# Regulador.net
KiCad netlist of a schematic drawn in Altium Designer
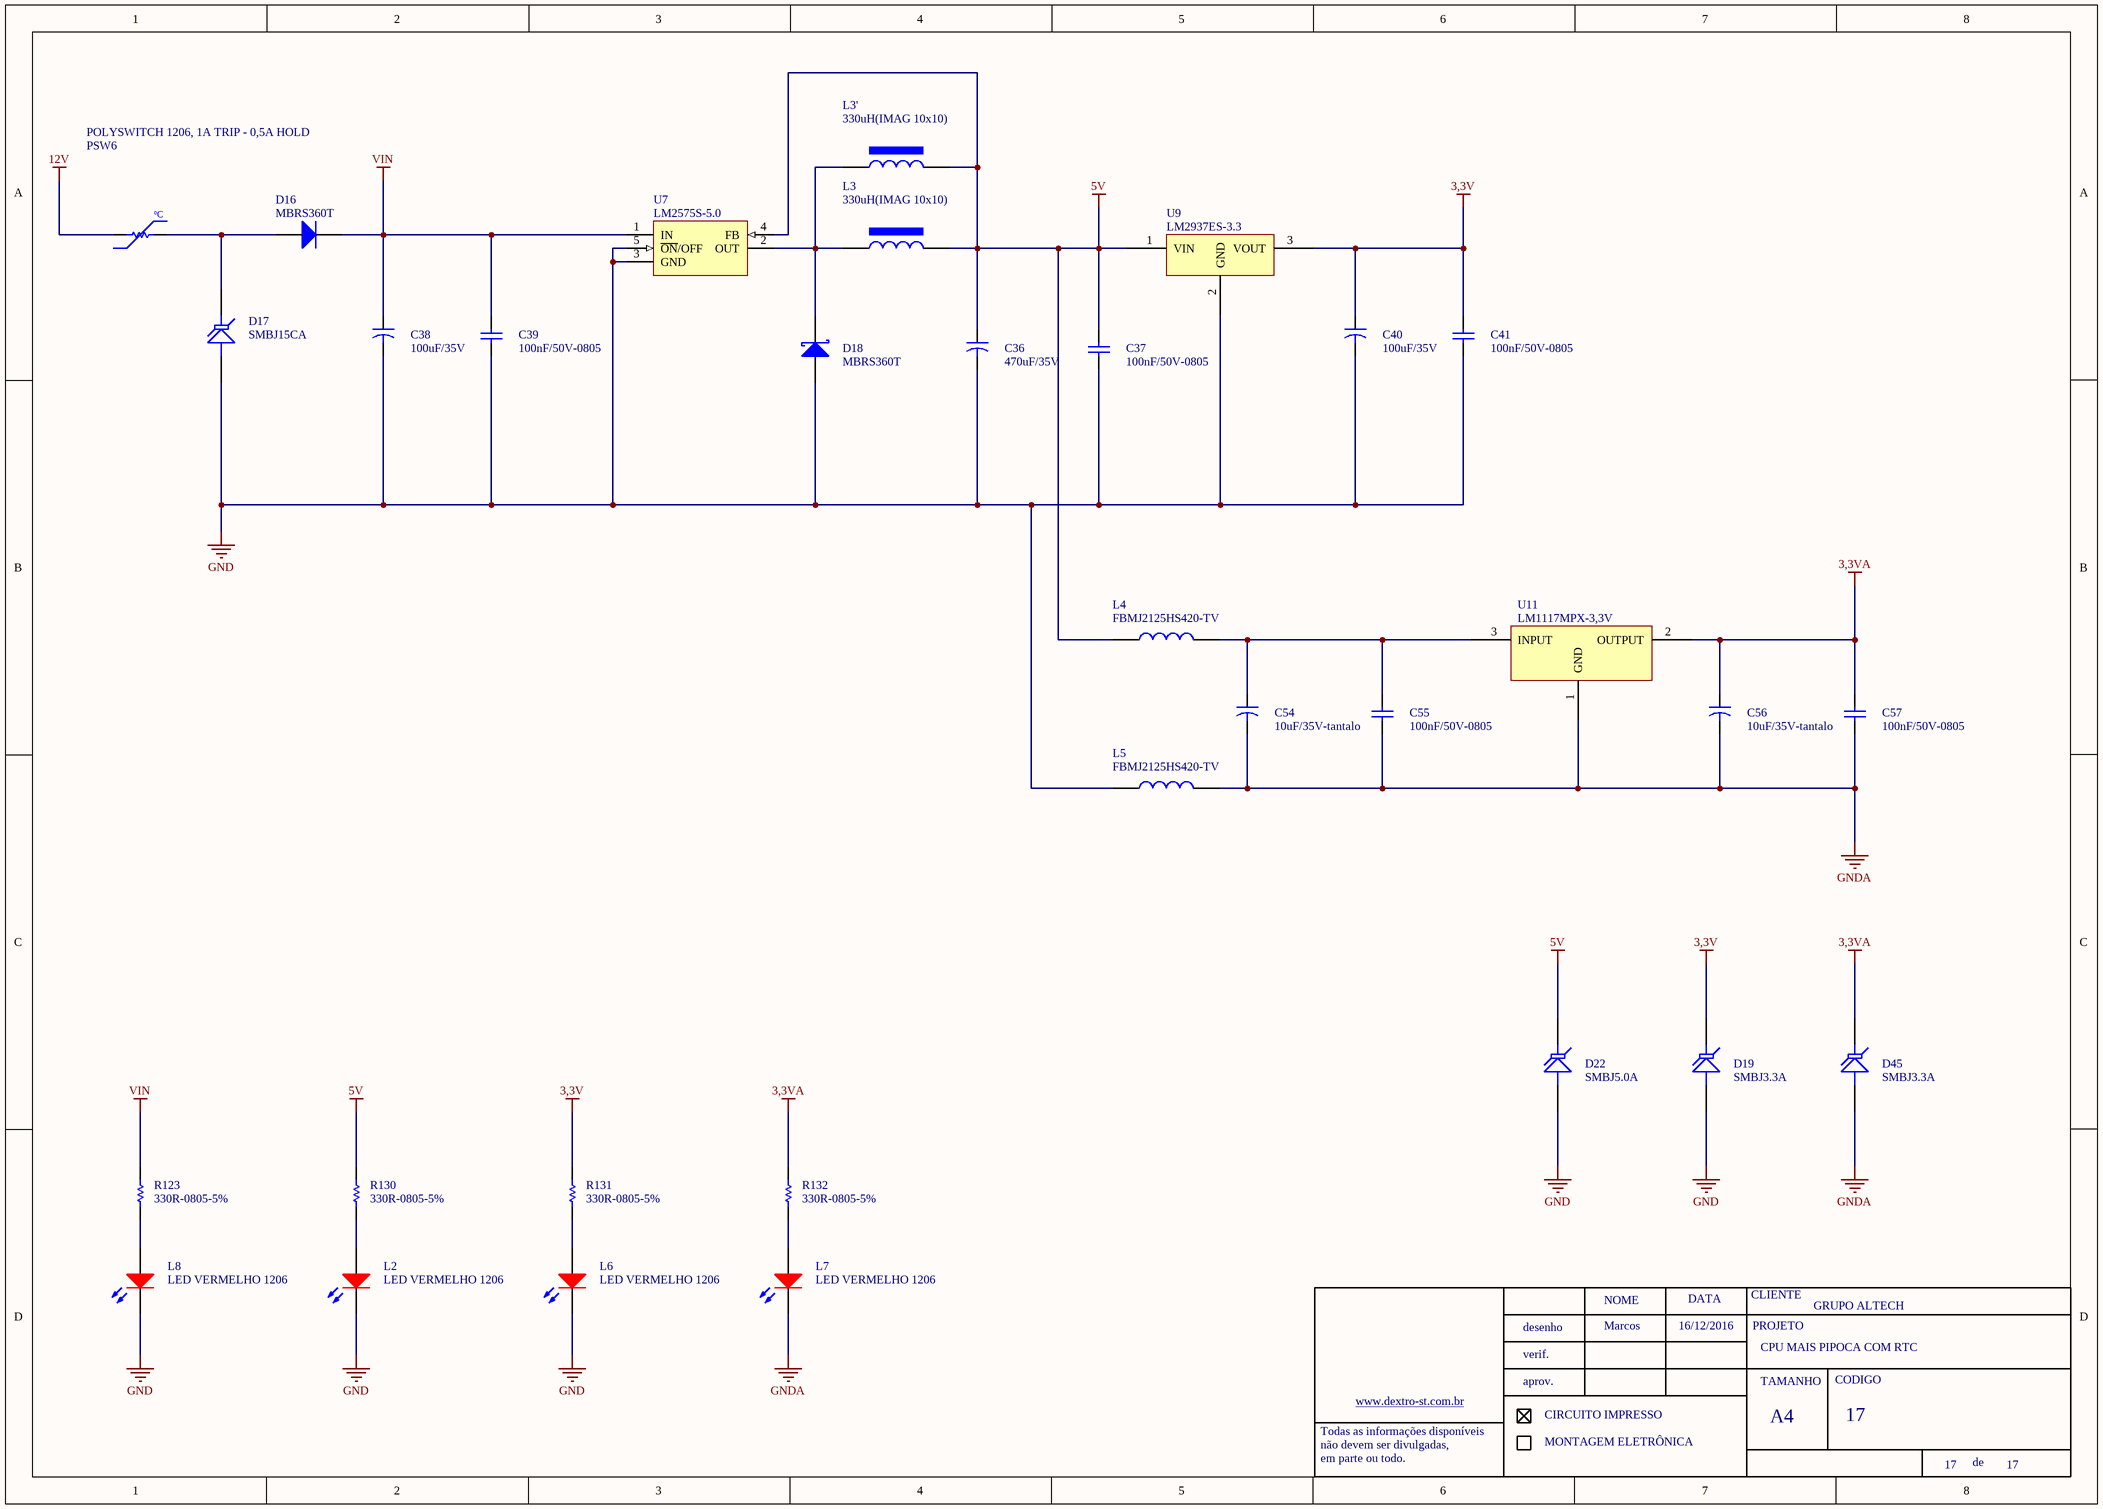
[diagram p0: Regulador.SchDoc]

(export (version "E")
  (design (tool "Eeschema 10.0.6"))
  (components
    (comp (ref "C36")
      (value "470uF/35V")
      (footprint "CAP POL 8x12mm")
      (description "100uF/50V")
      (libsource (lib "AquinoLib") (part "100uF/50V"))
    )
    (comp (ref "C37")
      (value "100nF/50V-0805")
      (footprint "0805-REVISADO ONDA")
      (description "100nF/50-0805-NPO")
      (libsource (lib "AquinoLib") (part "100nF/50-0805-NPO"))
    )
    (comp (ref "C38")
      (value "100uF/35V")
      (footprint "CAP POL 8x12mm")
      (description "100uF/50V")
      (libsource (lib "AquinoLib") (part "100uF/50V"))
    )
    (comp (ref "C39")
      (value "100nF/50V-0805")
      (footprint "0805-REVISADO ONDA")
      (description "100nF/50-0805-NPO")
      (libsource (lib "AquinoLib") (part "100nF/50-0805-NPO"))
    )
    (comp (ref "C40")
      (value "100uF/35V")
      (footprint "CAP POL 8x12mm")
      (description "100uF/50V")
      (libsource (lib "AquinoLib") (part "100uF/50V"))
    )
    (comp (ref "C41")
      (value "100nF/50V-0805")
      (footprint "0805-REVISADO ONDA")
      (description "100nF/50-0805-NPO")
      (libsource (lib "AquinoLib") (part "100nF/50-0805-NPO"))
    )
    (comp (ref "C54")
      (value "10uF/35V-tantalo")
      (footprint "tantalo vishay E")
      (libsource (lib "AquinoLib") (part "10uF/35V-tantalo"))
    )
    (comp (ref "C55")
      (value "100nF/50V-0805")
      (footprint "0805-REVISADO ONDA")
      (libsource (lib "AquinoLib") (part "100nF/50-0805-NPO"))
    )
    (comp (ref "C56")
      (value "10uF/35V-tantalo")
      (footprint "tantalo vishay E")
      (libsource (lib "AquinoLib") (part "10uF/35V-tantalo"))
    )
    (comp (ref "C57")
      (value "100nF/50V-0805")
      (footprint "0805-REVISADO ONDA")
      (libsource (lib "AquinoLib") (part "100nF/50-0805-NPO"))
    )
    (comp (ref "D16")
      (value "MBRS360T")
      (footprint "DO-214AB")
      (description "1N4007")
      (libsource (lib "AquinoLib") (part "1N4007"))
    )
    (comp (ref "D17")
      (value "SMBJ15CA")
      (footprint "DO-214AA")
      (description "SMBJ30.0A")
      (libsource (lib "AquinoLib") (part "SMBJ30.0A"))
    )
    (comp (ref "D18")
      (value "MBRS360T")
      (footprint "DO-214AB")
      (description "1N5819-SOD80")
      (libsource (lib "AquinoLib") (part "1N5819-SOD80"))
    )
    (comp (ref "D19")
      (value "SMBJ3.3A")
      (footprint "DO-214AA")
      (description "SMBJ5.0A")
      (libsource (lib "AquinoLib") (part "SMBJ5.0A"))
    )
    (comp (ref "D22")
      (value "SMBJ5.0A")
      (footprint "DO-214AA")
      (libsource (lib "AquinoLib") (part "SMBJ5.0A"))
    )
    (comp (ref "D45")
      (value "SMBJ3.3A")
      (footprint "DO-214AA")
      (description "SMBJ5.0A")
      (libsource (lib "AquinoLib") (part "SMBJ5.0A"))
    )
    (comp (ref "L2")
      (value "LED VERMELHO 1206")
      (footprint "LED 1206")
      (description "LED VERMELHO 0603 SMD")
      (libsource (lib "AquinoLib") (part "LED VERMELHO 0603 SMD"))
    )
    (comp (ref "L3")
      (value "330uH(IMAG 10x10)")
      (footprint "INDUTOR 47mH")
      (description "1mH-CNF15-26 AWG")
      (libsource (lib "AquinoLib") (part "indutor 1mH CNF15"))
    )
    (comp (ref "L3'")
      (value "330uH(IMAG 10x10)")
      (footprint "INDUTOR 47mH")
      (description "1mH-CNF15-26 AWG")
      (libsource (lib "AquinoLib") (part "indutor 1mH CNF15"))
    )
    (comp (ref "L4")
      (value "FBMJ2125HS420-TV")
      (footprint "0805-REVISADO ONDA")
      (description "FERRITE BEAD 2K7-100MHZ - 200 mA - 800mOHM DC")
      (libsource (lib "AquinoLib") (part "FERRITE BEAD 2K7-100MHZ - 200 mA - 800mOHM DC"))
    )
    (comp (ref "L5")
      (value "FBMJ2125HS420-TV")
      (footprint "0805-REVISADO ONDA")
      (description "FERRITE BEAD 2K7-100MHZ - 200 mA - 800mOHM DC")
      (libsource (lib "AquinoLib") (part "FERRITE BEAD 2K7-100MHZ - 200 mA - 800mOHM DC"))
    )
    (comp (ref "L6")
      (value "LED VERMELHO 1206")
      (footprint "LED 1206")
      (description "LED VERMELHO 0603 SMD")
      (libsource (lib "AquinoLib") (part "LED VERMELHO 0603 SMD"))
    )
    (comp (ref "L7")
      (value "LED VERMELHO 1206")
      (footprint "LED 1206")
      (description "LED VERMELHO 0603 SMD")
      (libsource (lib "AquinoLib") (part "LED VERMELHO 0603 SMD"))
    )
    (comp (ref "L8")
      (value "LED VERMELHO 1206")
      (footprint "LED 1206")
      (description "LED VERMELHO 0603 SMD")
      (libsource (lib "AquinoLib") (part "LED VERMELHO 0603 SMD"))
    )
    (comp (ref "PSW6")
      (value "POLYSWITCH 1206, 1A TRIP - 0,5A HOLD")
      (footprint "1206-REVISADO ONDA")
      (description "PTC 2A-120V")
      (libsource (lib "AquinoLib") (part "PTC 2A-120V"))
    )
    (comp (ref "R123")
      (value "330R-0805-5%")
      (footprint "0805-REVISADO ONDA")
      (description "1K-0805-5%")
      (libsource (lib "AquinoLib") (part "1K-0805-5%"))
    )
    (comp (ref "R130")
      (value "330R-0805-5%")
      (footprint "0805-REVISADO ONDA")
      (description "1K-0805-5%")
      (libsource (lib "AquinoLib") (part "1K-0805-5%"))
    )
    (comp (ref "R131")
      (value "330R-0805-5%")
      (footprint "0805-REVISADO ONDA")
      (description "1K-0805-5%")
      (libsource (lib "AquinoLib") (part "1K-0805-5%"))
    )
    (comp (ref "R132")
      (value "330R-0805-5%")
      (footprint "0805-REVISADO ONDA")
      (description "1K-0805-5%")
      (libsource (lib "AquinoLib") (part "1K-0805-5%"))
    )
    (comp (ref "U7")
      (value "LM2575S-5.0")
      (footprint "TO-263-5")
      (libsource (lib "AquinoLib") (part "LM2575S-5.0"))
    )
    (comp (ref "U9")
      (value "LM2937ES-3.3")
      (footprint "TO-263")
      (description "LM2937")
      (libsource (lib "ChaveDigital3") (part "LM3940IT-3.3-TO220"))
    )
    (comp (ref "U11")
      (value "LM1117MPX-3,3V")
      (footprint "SOT223")
      (libsource (lib "AquinoLib") (part "LM1117MPX-3,3V-SOT223"))
    )
  )
  (nets
    (net (code "1") (name "3,3V") (class "Default")
      (node (ref "C40") (pin "1") (pinfunction "1_1") (pintype "passive"))
      (node (ref "C41") (pin "2") (pinfunction "2_2") (pintype "passive"))
      (node (ref "D19") (pin "2") (pinfunction "K_2") (pintype "passive"))
      (node (ref "R131") (pin "2") (pinfunction "2_2") (pintype "passive"))
      (node (ref "U9") (pin "3") (pinfunction "VOUT_3") (pintype "passive"))
    )
    (net (code "2") (name "3,3VA") (class "Default")
      (node (ref "C56") (pin "1") (pinfunction "1_1") (pintype "passive"))
      (node (ref "C57") (pin "2") (pinfunction "2_2") (pintype "passive"))
      (node (ref "D45") (pin "2") (pinfunction "K_2") (pintype "passive"))
      (node (ref "R132") (pin "2") (pinfunction "2_2") (pintype "passive"))
      (node (ref "U11") (pin "2") (pinfunction "OUTPUT_2") (pintype "passive"))
    )
    (net (code "3") (name "5V") (class "Default")
      (node (ref "C36") (pin "1") (pinfunction "1_1") (pintype "passive"))
      (node (ref "C37") (pin "2") (pinfunction "2_2") (pintype "passive"))
      (node (ref "D22") (pin "2") (pinfunction "K_2") (pintype "passive"))
      (node (ref "L3") (pin "1") (pinfunction "1_1") (pintype "passive"))
      (node (ref "L3'") (pin "1") (pinfunction "1_1") (pintype "passive"))
      (node (ref "L4") (pin "1") (pinfunction "1_1") (pintype "passive"))
      (node (ref "R130") (pin "2") (pinfunction "2_2") (pintype "passive"))
      (node (ref "U7") (pin "4") (pinfunction "FB_4") (pintype "input"))
      (node (ref "U9") (pin "1") (pinfunction "VIN_1") (pintype "passive"))
    )
    (net (code "4") (name "12V") (class "Default")
      (node (ref "PSW6") (pin "1") (pinfunction "1_1") (pintype "passive"))
    )
    (net (code "5") (name "GND") (class "Default")
      (node (ref "C36") (pin "2") (pinfunction "2_2") (pintype "passive"))
      (node (ref "C37") (pin "1") (pinfunction "1_1") (pintype "passive"))
      (node (ref "C38") (pin "2") (pinfunction "2_2") (pintype "passive"))
      (node (ref "C39") (pin "1") (pinfunction "1_1") (pintype "passive"))
      (node (ref "C40") (pin "2") (pinfunction "2_2") (pintype "passive"))
      (node (ref "C41") (pin "1") (pinfunction "1_1") (pintype "passive"))
      (node (ref "D17") (pin "1") (pinfunction "A_1") (pintype "passive"))
      (node (ref "D18") (pin "1") (pinfunction "A_1") (pintype "passive"))
      (node (ref "D19") (pin "1") (pinfunction "A_1") (pintype "passive"))
      (node (ref "D22") (pin "1") (pinfunction "A_1") (pintype "passive"))
      (node (ref "L2") (pin "2") (pinfunction "K_2") (pintype "passive"))
      (node (ref "L5") (pin "1") (pinfunction "1_1") (pintype "passive"))
      (node (ref "L6") (pin "2") (pinfunction "K_2") (pintype "passive"))
      (node (ref "L8") (pin "2") (pinfunction "K_2") (pintype "passive"))
      (node (ref "U7") (pin "3") (pinfunction "GND_3") (pintype "power_in"))
      (node (ref "U7") (pin "5") (pinfunction "~{ON}/OFF_5") (pintype "input"))
      (node (ref "U9") (pin "2") (pinfunction "GND_2") (pintype "passive"))
    )
    (net (code "6") (name "GNDA") (class "Default")
      (node (ref "C54") (pin "2") (pinfunction "2_2") (pintype "passive"))
      (node (ref "C55") (pin "1") (pinfunction "1_1") (pintype "passive"))
      (node (ref "C56") (pin "2") (pinfunction "2_2") (pintype "passive"))
      (node (ref "C57") (pin "1") (pinfunction "1_1") (pintype "passive"))
      (node (ref "D45") (pin "1") (pinfunction "A_1") (pintype "passive"))
      (node (ref "L5") (pin "2") (pinfunction "2_2") (pintype "passive"))
      (node (ref "L7") (pin "2") (pinfunction "K_2") (pintype "passive"))
      (node (ref "U11") (pin "1") (pinfunction "GND_1") (pintype "passive"))
    )
    (net (code "7") (name "Net-(D16-A)") (class "Default")
      (node (ref "D16") (pin "1") (pinfunction "A_1") (pintype "passive"))
      (node (ref "D17") (pin "2") (pinfunction "K_2") (pintype "passive"))
      (node (ref "PSW6") (pin "2") (pinfunction "2_2") (pintype "passive"))
    )
    (net (code "8") (name "Net-(D18-K)") (class "Default")
      (node (ref "D18") (pin "2") (pinfunction "K_2") (pintype "passive"))
      (node (ref "L3") (pin "2") (pinfunction "2_2") (pintype "passive"))
      (node (ref "L3'") (pin "2") (pinfunction "2_2") (pintype "passive"))
      (node (ref "U7") (pin "2") (pinfunction "OUT_2") (pintype "power_in"))
    )
    (net (code "9") (name "Net-(L2-A)") (class "Default")
      (node (ref "L2") (pin "1") (pinfunction "A_1") (pintype "passive"))
      (node (ref "R130") (pin "1") (pinfunction "1_1") (pintype "passive"))
    )
    (net (code "10") (name "Net-(L6-A)") (class "Default")
      (node (ref "L6") (pin "1") (pinfunction "A_1") (pintype "passive"))
      (node (ref "R131") (pin "1") (pinfunction "1_1") (pintype "passive"))
    )
    (net (code "11") (name "Net-(L7-A)") (class "Default")
      (node (ref "L7") (pin "1") (pinfunction "A_1") (pintype "passive"))
      (node (ref "R132") (pin "1") (pinfunction "1_1") (pintype "passive"))
    )
    (net (code "12") (name "Net-(L8-A)") (class "Default")
      (node (ref "L8") (pin "1") (pinfunction "A_1") (pintype "passive"))
      (node (ref "R123") (pin "1") (pinfunction "1_1") (pintype "passive"))
    )
    (net (code "13") (name "Net-(U11-INPUT)") (class "Default")
      (node (ref "C54") (pin "1") (pinfunction "1_1") (pintype "passive"))
      (node (ref "C55") (pin "2") (pinfunction "2_2") (pintype "passive"))
      (node (ref "L4") (pin "2") (pinfunction "2_2") (pintype "passive"))
      (node (ref "U11") (pin "3") (pinfunction "INPUT_3") (pintype "passive"))
    )
    (net (code "14") (name "VIN") (class "Default")
      (node (ref "C38") (pin "1") (pinfunction "1_1") (pintype "passive"))
      (node (ref "C39") (pin "2") (pinfunction "2_2") (pintype "passive"))
      (node (ref "D16") (pin "2") (pinfunction "K_2") (pintype "passive"))
      (node (ref "R123") (pin "2") (pinfunction "2_2") (pintype "passive"))
      (node (ref "U7") (pin "1") (pinfunction "IN_1") (pintype "power_in"))
    )
  )
)
